# ALU_1_0.net
KiCad netlist of a schematic drawn in EAGLE
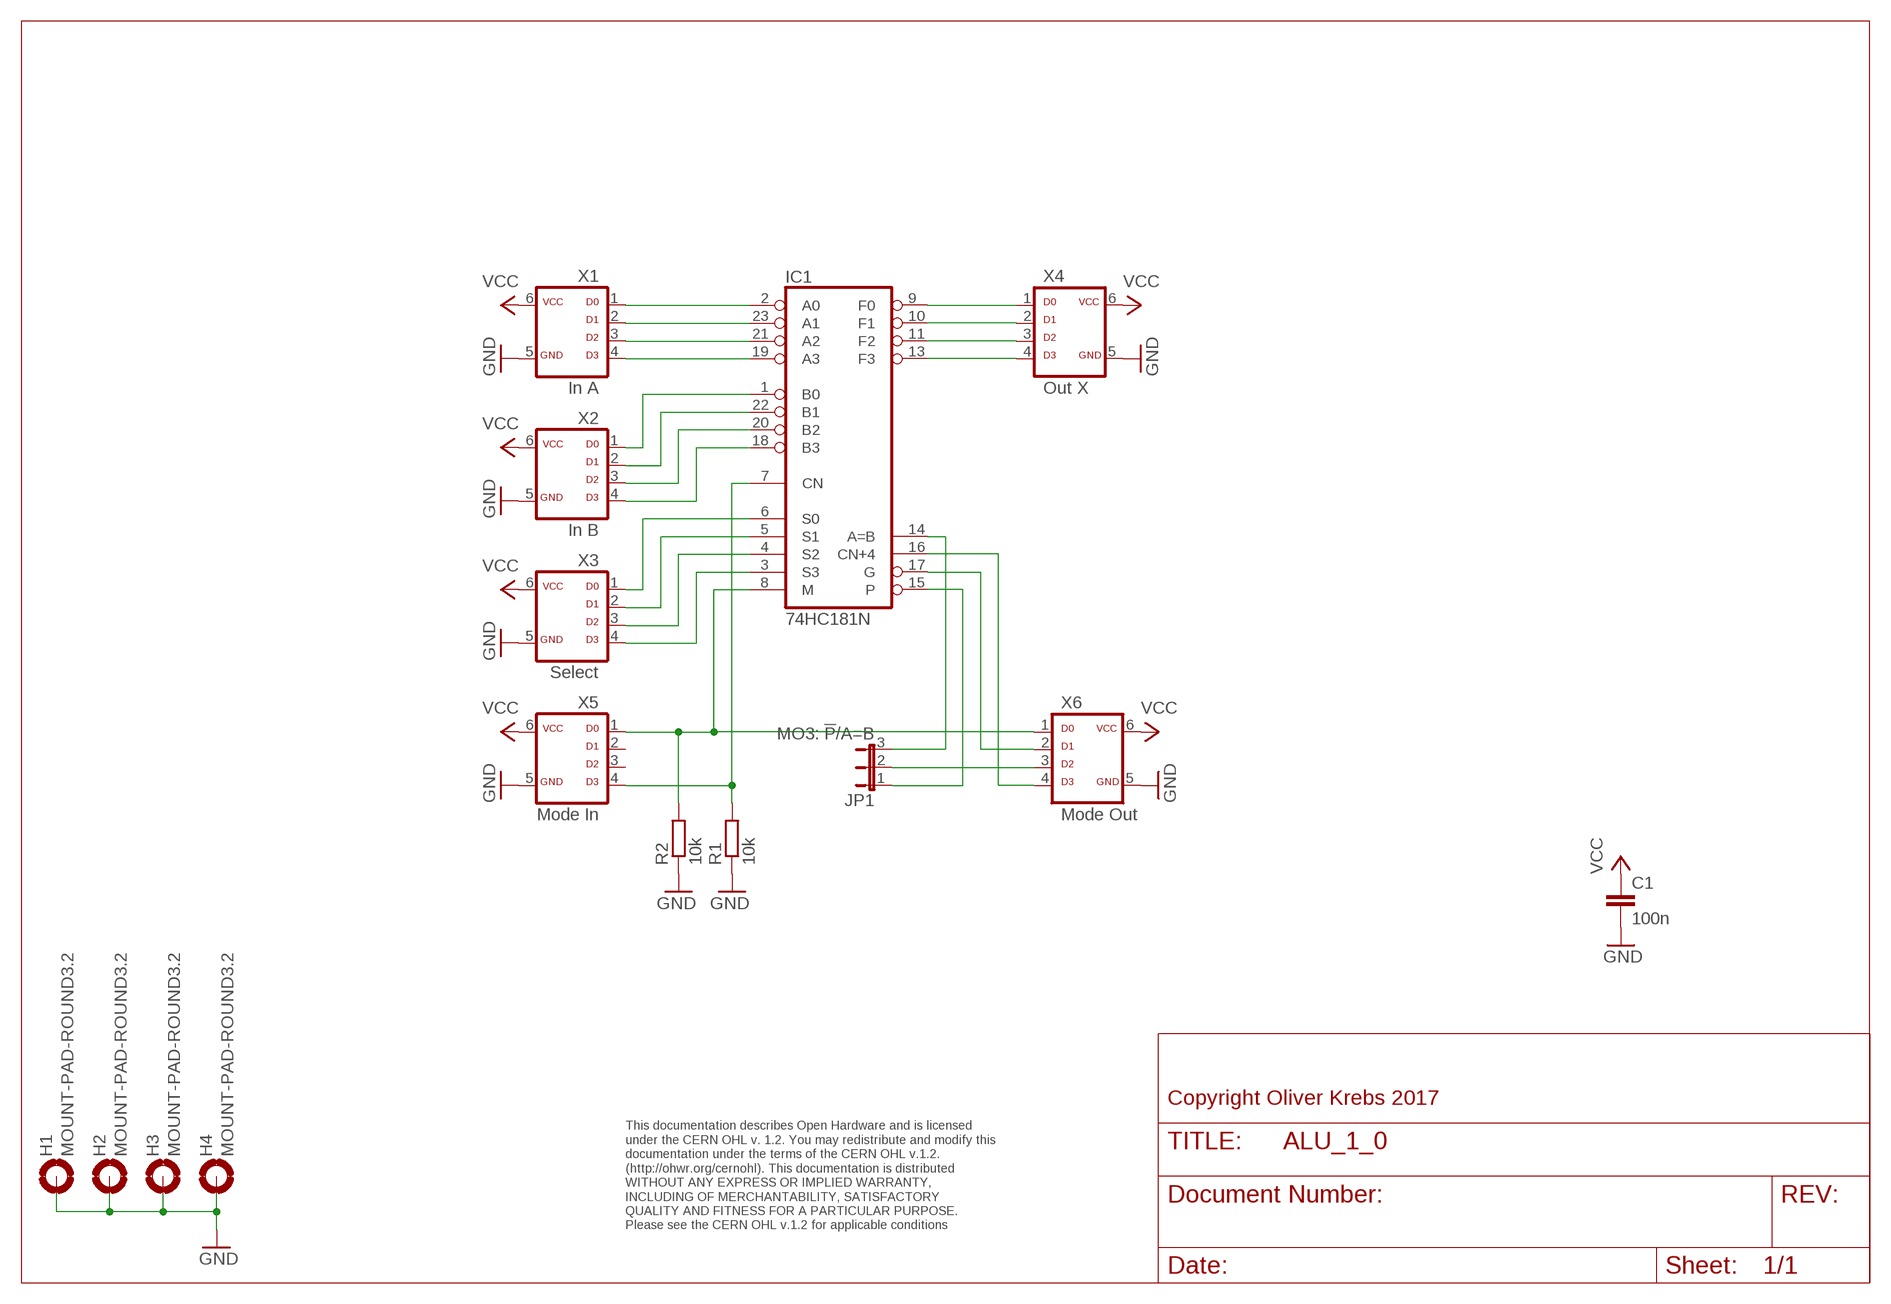
[diagram p0: schematic, sheet 1]

(export (version "E")
  (design (tool "Eeschema 10.0.6"))
  (components
    (comp (ref "C1")
      (value "100n")
      (footprint "eagle-import:C050-025X075")
      (libsource (lib "eagle-import") (part "C-EU050-025X075"))
    )
    (comp (ref "H1")
      (value "MOUNT-PAD-ROUND3.2")
      (footprint "eagle-import:3,2-PAD")
      (libsource (lib "eagle-import") (part "MOUNT-PAD-ROUND3.2"))
    )
    (comp (ref "H2")
      (value "MOUNT-PAD-ROUND3.2")
      (footprint "eagle-import:3,2-PAD")
      (libsource (lib "eagle-import") (part "MOUNT-PAD-ROUND3.2"))
    )
    (comp (ref "H3")
      (value "MOUNT-PAD-ROUND3.2")
      (footprint "eagle-import:3,2-PAD")
      (libsource (lib "eagle-import") (part "MOUNT-PAD-ROUND3.2"))
    )
    (comp (ref "H4")
      (value "MOUNT-PAD-ROUND3.2")
      (footprint "eagle-import:3,2-PAD")
      (libsource (lib "eagle-import") (part "MOUNT-PAD-ROUND3.2"))
    )
    (comp (ref "IC1")
      (value "74HC181N")
      (footprint "eagle-import:DIL24-6")
      (libsource (lib "eagle-import") (part "74181NHC"))
    )
    (comp (ref "JP1")
      (value "MO3: !P!/A=B")
      (footprint "eagle-import:JP2")
      (libsource (lib "eagle-import") (part "JP2EJP2"))
    )
    (comp (ref "R1")
      (value "10k")
      (footprint "eagle-import:0207_10")
      (libsource (lib "eagle-import") (part "R-EU_0207/10"))
    )
    (comp (ref "R2")
      (value "10k")
      (footprint "eagle-import:0207_10")
      (libsource (lib "eagle-import") (part "R-EU_0207/10"))
    )
    (comp (ref "X1")
      (value "In A")
      (footprint "eagle-import:ML-6")
      (libsource (lib "eagle-import") (part "ML6D"))
    )
    (comp (ref "X2")
      (value "In B")
      (footprint "eagle-import:ML-6")
      (libsource (lib "eagle-import") (part "ML6D"))
    )
    (comp (ref "X3")
      (value "Select")
      (footprint "eagle-import:ML-6")
      (libsource (lib "eagle-import") (part "ML6D"))
    )
    (comp (ref "X4")
      (value "Out X")
      (footprint "eagle-import:ML-6")
      (libsource (lib "eagle-import") (part "ML6D"))
    )
    (comp (ref "X5")
      (value "Mode In")
      (footprint "eagle-import:ML-6")
      (libsource (lib "eagle-import") (part "ML6D"))
    )
    (comp (ref "X6")
      (value "Mode Out")
      (footprint "eagle-import:ML-6")
      (libsource (lib "eagle-import") (part "ML6D"))
    )
  )
  (nets
    (net (code "1") (name "GND") (class "Default")
      (node (ref "C1") (pin "2") (pinfunction "2_2") (pintype "passive"))
      (node (ref "H1") (pin "B3,2") (pinfunction "MOUNT_B3,2") (pintype "passive"))
      (node (ref "H2") (pin "B3,2") (pinfunction "MOUNT_B3,2") (pintype "passive"))
      (node (ref "H3") (pin "B3,2") (pinfunction "MOUNT_B3,2") (pintype "passive"))
      (node (ref "H4") (pin "B3,2") (pinfunction "MOUNT_B3,2") (pintype "passive"))
      (node (ref "R1") (pin "1") (pinfunction "1_1") (pintype "passive"))
      (node (ref "R2") (pin "1") (pinfunction "1_1") (pintype "passive"))
      (node (ref "X1") (pin "5") (pinfunction "5_5") (pintype "passive"))
      (node (ref "X2") (pin "5") (pinfunction "5_5") (pintype "passive"))
      (node (ref "X3") (pin "5") (pinfunction "5_5") (pintype "passive"))
      (node (ref "X4") (pin "5") (pinfunction "5_5") (pintype "passive"))
      (node (ref "X5") (pin "5") (pinfunction "5_5") (pintype "passive"))
      (node (ref "X6") (pin "5") (pinfunction "5_5") (pintype "passive"))
    )
    (net (code "2") (name "Net-(IC1A-A0)") (class "Default")
      (node (ref "IC1") (pin "2") (pinfunction "A0_2") (pintype "input"))
      (node (ref "X1") (pin "1") (pinfunction "1_1") (pintype "passive"))
    )
    (net (code "3") (name "Net-(IC1A-A1)") (class "Default")
      (node (ref "IC1") (pin "23") (pinfunction "A1_23") (pintype "input"))
      (node (ref "X1") (pin "2") (pinfunction "2_2") (pintype "passive"))
    )
    (net (code "4") (name "Net-(IC1A-A2)") (class "Default")
      (node (ref "IC1") (pin "21") (pinfunction "A2_21") (pintype "input"))
      (node (ref "X1") (pin "3") (pinfunction "3_3") (pintype "passive"))
    )
    (net (code "5") (name "Net-(IC1A-A3)") (class "Default")
      (node (ref "IC1") (pin "19") (pinfunction "A3_19") (pintype "input"))
      (node (ref "X1") (pin "4") (pinfunction "4_4") (pintype "passive"))
    )
    (net (code "6") (name "Net-(IC1A-A=B)") (class "Default")
      (node (ref "IC1") (pin "14") (pinfunction "A=B_14") (pintype "output"))
      (node (ref "JP1") (pin "3") (pinfunction "3_3") (pintype "passive"))
    )
    (net (code "7") (name "Net-(IC1A-B0)") (class "Default")
      (node (ref "IC1") (pin "1") (pinfunction "B0_1") (pintype "input"))
      (node (ref "X2") (pin "1") (pinfunction "1_1") (pintype "passive"))
    )
    (net (code "8") (name "Net-(IC1A-B1)") (class "Default")
      (node (ref "IC1") (pin "22") (pinfunction "B1_22") (pintype "input"))
      (node (ref "X2") (pin "2") (pinfunction "2_2") (pintype "passive"))
    )
    (net (code "9") (name "Net-(IC1A-B2)") (class "Default")
      (node (ref "IC1") (pin "20") (pinfunction "B2_20") (pintype "input"))
      (node (ref "X2") (pin "3") (pinfunction "3_3") (pintype "passive"))
    )
    (net (code "10") (name "Net-(IC1A-B3)") (class "Default")
      (node (ref "IC1") (pin "18") (pinfunction "B3_18") (pintype "input"))
      (node (ref "X2") (pin "4") (pinfunction "4_4") (pintype "passive"))
    )
    (net (code "11") (name "Net-(IC1A-CN)") (class "Default")
      (node (ref "IC1") (pin "7") (pinfunction "CN_7") (pintype "input"))
      (node (ref "R1") (pin "2") (pinfunction "2_2") (pintype "passive"))
      (node (ref "X5") (pin "4") (pinfunction "4_4") (pintype "passive"))
    )
    (net (code "12") (name "Net-(IC1A-CN+4)") (class "Default")
      (node (ref "IC1") (pin "16") (pinfunction "CN+4_16") (pintype "output"))
      (node (ref "X6") (pin "4") (pinfunction "4_4") (pintype "passive"))
    )
    (net (code "13") (name "Net-(IC1A-F0)") (class "Default")
      (node (ref "IC1") (pin "9") (pinfunction "F0_9") (pintype "output"))
      (node (ref "X4") (pin "1") (pinfunction "1_1") (pintype "passive"))
    )
    (net (code "14") (name "Net-(IC1A-F1)") (class "Default")
      (node (ref "IC1") (pin "10") (pinfunction "F1_10") (pintype "output"))
      (node (ref "X4") (pin "2") (pinfunction "2_2") (pintype "passive"))
    )
    (net (code "15") (name "Net-(IC1A-F2)") (class "Default")
      (node (ref "IC1") (pin "11") (pinfunction "F2_11") (pintype "output"))
      (node (ref "X4") (pin "3") (pinfunction "3_3") (pintype "passive"))
    )
    (net (code "16") (name "Net-(IC1A-F3)") (class "Default")
      (node (ref "IC1") (pin "13") (pinfunction "F3_13") (pintype "output"))
      (node (ref "X4") (pin "4") (pinfunction "4_4") (pintype "passive"))
    )
    (net (code "17") (name "Net-(IC1A-G)") (class "Default")
      (node (ref "IC1") (pin "17") (pinfunction "G_17") (pintype "output"))
      (node (ref "X6") (pin "2") (pinfunction "2_2") (pintype "passive"))
    )
    (net (code "18") (name "Net-(IC1A-M)") (class "Default")
      (node (ref "IC1") (pin "8") (pinfunction "M_8") (pintype "input"))
      (node (ref "R2") (pin "2") (pinfunction "2_2") (pintype "passive"))
      (node (ref "X5") (pin "1") (pinfunction "1_1") (pintype "passive"))
      (node (ref "X6") (pin "1") (pinfunction "1_1") (pintype "passive"))
    )
    (net (code "19") (name "Net-(IC1A-P)") (class "Default")
      (node (ref "IC1") (pin "15") (pinfunction "P_15") (pintype "output"))
      (node (ref "JP1") (pin "1") (pinfunction "1_1") (pintype "passive"))
    )
    (net (code "20") (name "Net-(IC1A-S0)") (class "Default")
      (node (ref "IC1") (pin "6") (pinfunction "S0_6") (pintype "input"))
      (node (ref "X3") (pin "1") (pinfunction "1_1") (pintype "passive"))
    )
    (net (code "21") (name "Net-(IC1A-S1)") (class "Default")
      (node (ref "IC1") (pin "5") (pinfunction "S1_5") (pintype "input"))
      (node (ref "X3") (pin "2") (pinfunction "2_2") (pintype "passive"))
    )
    (net (code "22") (name "Net-(IC1A-S2)") (class "Default")
      (node (ref "IC1") (pin "4") (pinfunction "S2_4") (pintype "input"))
      (node (ref "X3") (pin "3") (pinfunction "3_3") (pintype "passive"))
    )
    (net (code "23") (name "Net-(IC1A-S3)") (class "Default")
      (node (ref "IC1") (pin "3") (pinfunction "S3_3") (pintype "input"))
      (node (ref "X3") (pin "4") (pinfunction "4_4") (pintype "passive"))
    )
    (net (code "24") (name "Net-(JP1-Pad2)") (class "Default")
      (node (ref "JP1") (pin "2") (pinfunction "2_2") (pintype "passive"))
      (node (ref "X6") (pin "3") (pinfunction "3_3") (pintype "passive"))
    )
    (net (code "25") (name "VCC") (class "Default")
      (node (ref "C1") (pin "1") (pinfunction "1_1") (pintype "passive"))
      (node (ref "X1") (pin "6") (pinfunction "6_6") (pintype "passive"))
      (node (ref "X2") (pin "6") (pinfunction "6_6") (pintype "passive"))
      (node (ref "X3") (pin "6") (pinfunction "6_6") (pintype "passive"))
      (node (ref "X4") (pin "6") (pinfunction "6_6") (pintype "passive"))
      (node (ref "X5") (pin "6") (pinfunction "6_6") (pintype "passive"))
      (node (ref "X6") (pin "6") (pinfunction "6_6") (pintype "passive"))
    )
    (net (code "26") (name "unconnected-(X5-Pad2)") (class "Default")
      (node (ref "X5") (pin "2") (pinfunction "2_2") (pintype "passive"))
    )
    (net (code "27") (name "unconnected-(X5-Pad3)") (class "Default")
      (node (ref "X5") (pin "3") (pinfunction "3_3") (pintype "passive"))
    )
  )
)
